# NEOS_CAN.net
KiCad netlist of a schematic drawn in Altium Designer
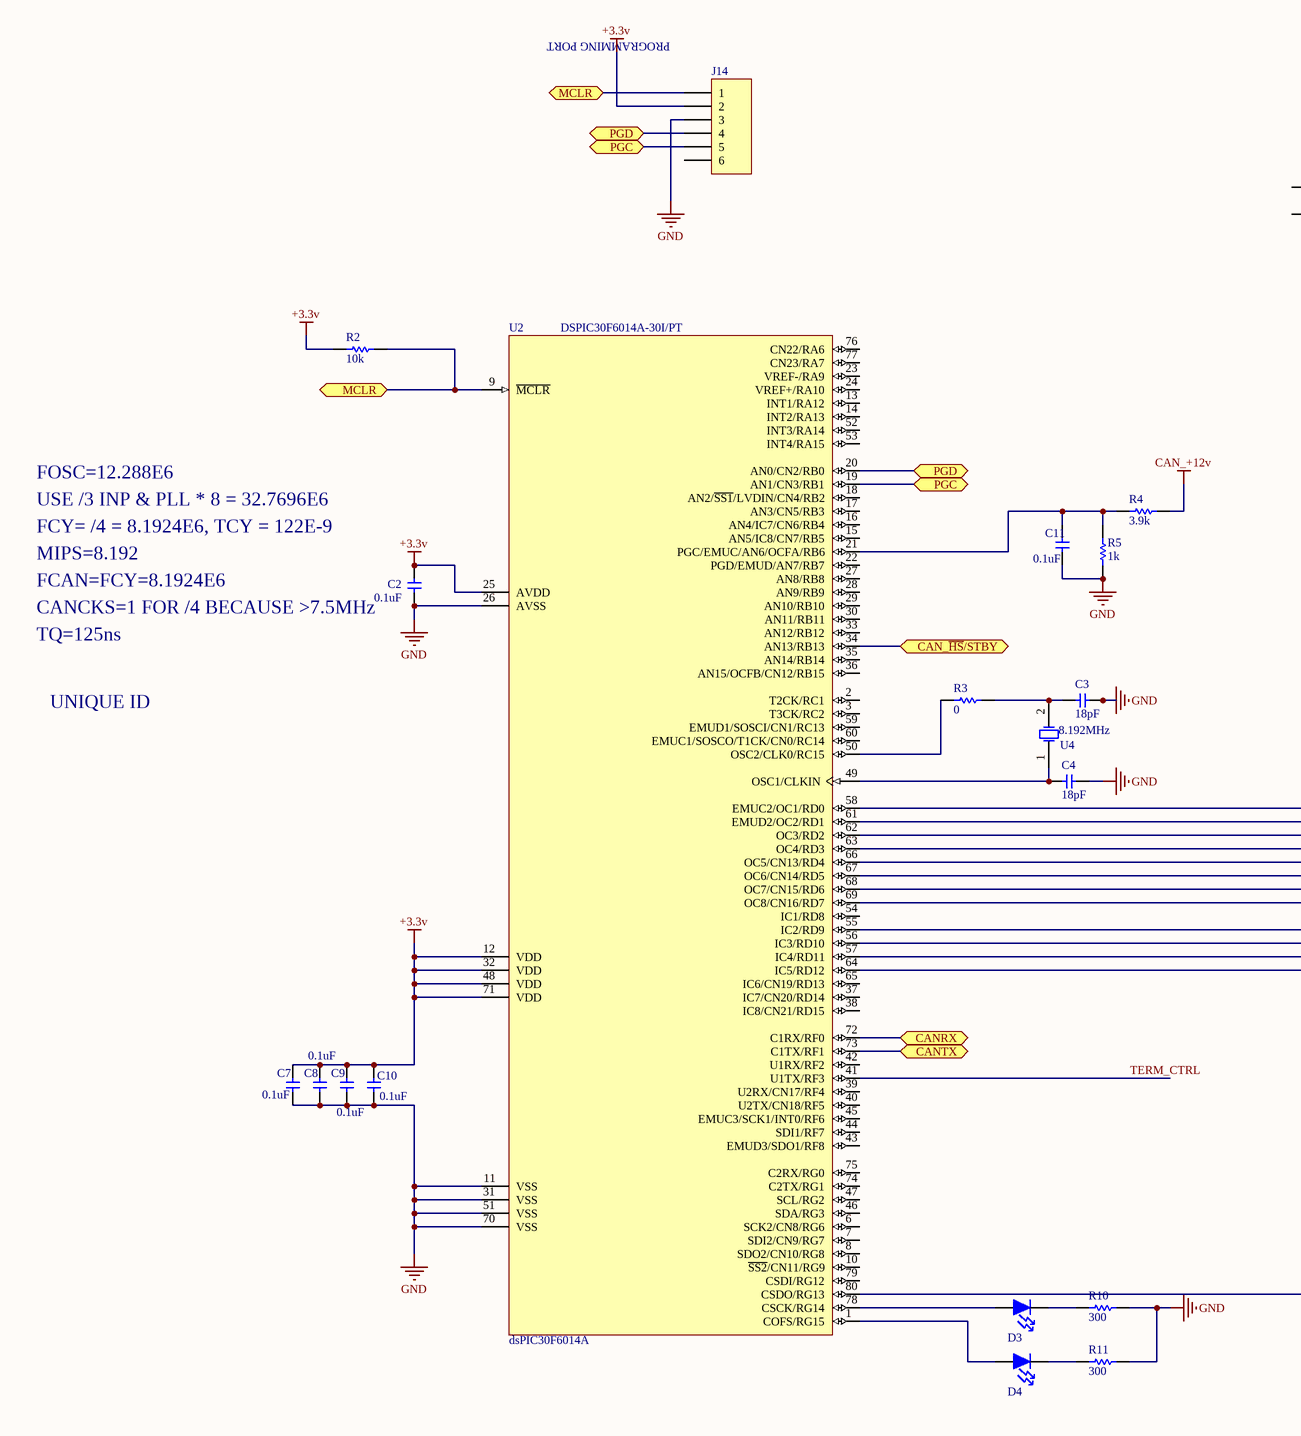
[diagram p0: NEOS_CAN.SchDoc, bottom left]
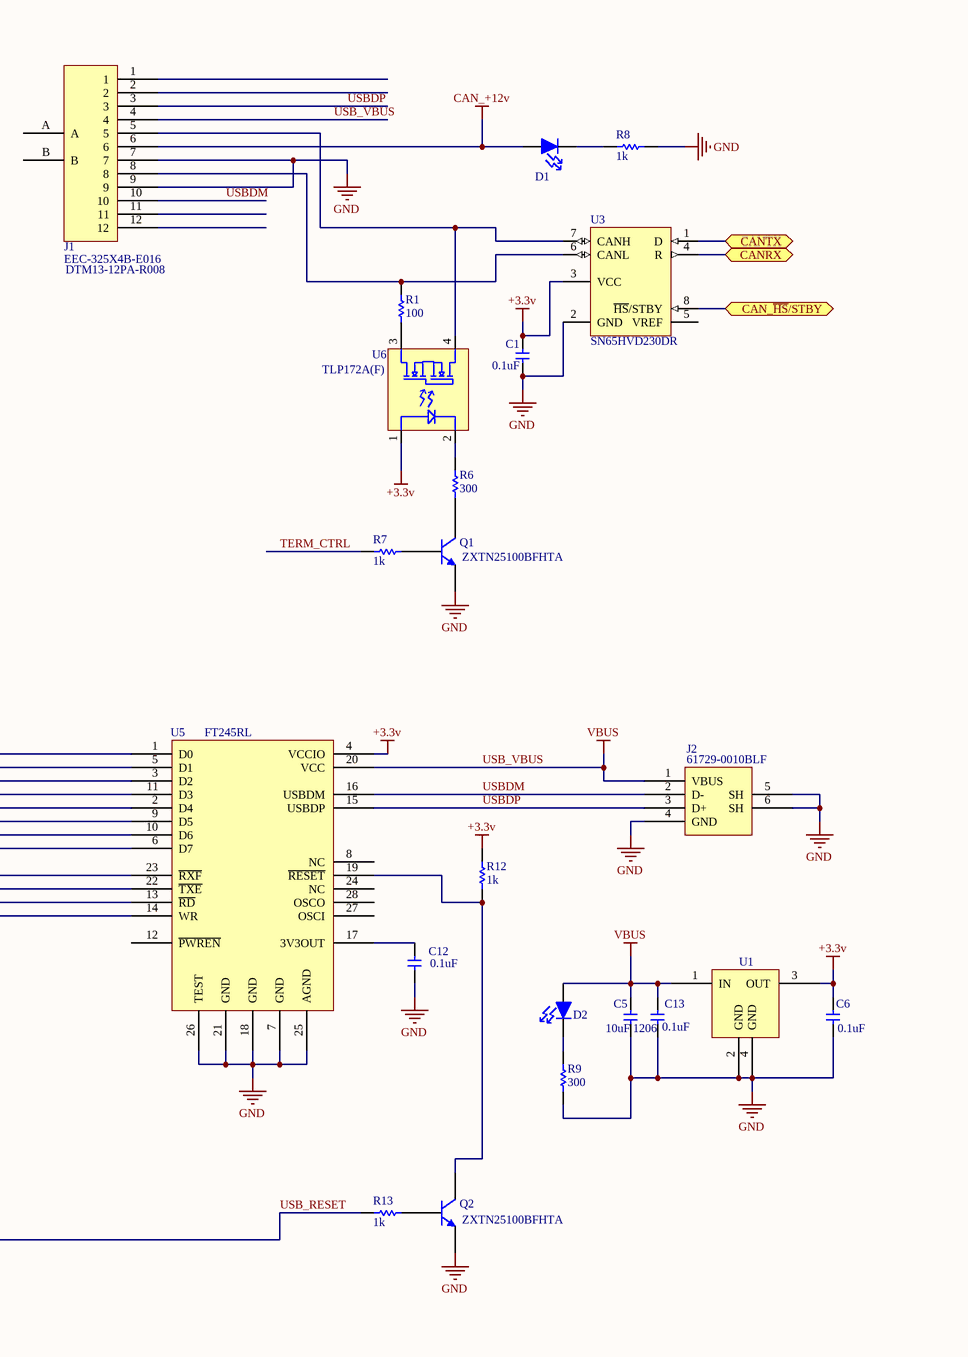
[diagram p1: NEOS_CAN.SchDoc, bottom middle]
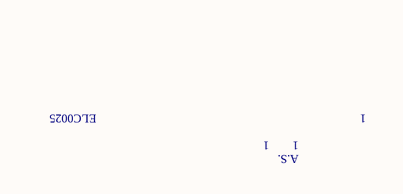
[diagram p2: NEOS_CAN.SchDoc, bottom right]

(export (version "E")
  (design (tool "Eeschema 10.0.6"))
  (components
    (comp (ref "C1")
      (value "0.1uF")
      (footprint "0603")
      (fields
        (field (name "MANUFACTURER") "Murata Electronics North America")
        (field (name "MANUFACTURER PART NUMBER") "GRM188R71C104KA01D")
        (field (name "SOURCE") "Digikey")
      )
      (libsource (lib "PlayworldRCL") (part "C"))
    )
    (comp (ref "C2")
      (value "0.1uF")
      (footprint "0603")
      (fields
        (field (name "MANUFACTURER") "Murata Electronics North America")
        (field (name "MANUFACTURER PART NUMBER") "GRM188R71C104KA01D")
        (field (name "SOURCE") "Digikey")
      )
      (libsource (lib "PlayworldRCL") (part "C"))
    )
    (comp (ref "C3")
      (value "18pF")
      (footprint "0603")
      (description "CAP CER 18PF 50V 5% C0G 0603")
      (fields
        (field (name "MANUFACTURER") "Murata Electronics North America")
        (field (name "MANUFACTURER PART NUMBER") "GRM1885C1H180JA01D")
        (field (name "SOURCE") "Digikey")
      )
      (libsource (lib "PlayworldRCL") (part "C"))
    )
    (comp (ref "C4")
      (value "18pF")
      (footprint "0603")
      (description "CAP CER 18PF 50V 5% C0G 0603")
      (fields
        (field (name "MANUFACTURER") "Murata Electronics North America")
        (field (name "SOURCE") "Digikey")
      )
      (libsource (lib "PlayworldRCL") (part "C"))
    )
    (comp (ref "C5")
      (value "10uF 1206")
      (footprint "1206")
      (fields
        (field (name "MANUFACTURER") "Murata Electronics North America")
        (field (name "MANUFACTURER PART NUMBER") "GRM31CF51E106ZA01L")
        (field (name "Comment") "C")
        (field (name "SOURCE") "Digikey")
      )
      (libsource (lib "PlayworldRCL") (part "C"))
    )
    (comp (ref "C6")
      (value "0.1uF")
      (footprint "0805")
      (fields
        (field (name "MANUFACTURER") "Murata Electronics North America")
        (field (name "MANUFACTURER PART NUMBER") "GRM188R71C104KA01D")
        (field (name "Comment") "C")
        (field (name "SOURCE") "Digikey")
      )
      (libsource (lib "PlayworldRCL") (part "C"))
    )
    (comp (ref "C7")
      (value "0.1uF")
      (footprint "0603")
      (fields
        (field (name "MANUFACTURER") "Murata Electronics North America")
        (field (name "MANUFACTURER PART NUMBER") "GRM188R71C104KA01D")
        (field (name "SOURCE") "Digikey")
      )
      (libsource (lib "PlayworldRCL") (part "C"))
    )
    (comp (ref "C8")
      (value "0.1uF")
      (footprint "0603")
      (fields
        (field (name "MANUFACTURER") "Murata Electronics North America")
        (field (name "MANUFACTURER PART NUMBER") "GRM188R71C104KA01D")
        (field (name "SOURCE") "Digikey")
      )
      (libsource (lib "PlayworldRCL") (part "C"))
    )
    (comp (ref "C9")
      (value "0.1uF")
      (footprint "0603")
      (fields
        (field (name "MANUFACTURER") "Murata Electronics North America")
        (field (name "MANUFACTURER PART NUMBER") "GRM188R71C104KA01D")
        (field (name "SOURCE") "Digikey")
      )
      (libsource (lib "PlayworldRCL") (part "C"))
    )
    (comp (ref "C10")
      (value "0.1uF")
      (footprint "0603")
      (fields
        (field (name "MANUFACTURER") "Murata Electronics North America")
        (field (name "MANUFACTURER PART NUMBER") "GRM188R71C104KA01D")
        (field (name "SOURCE") "Digikey")
      )
      (libsource (lib "PlayworldRCL") (part "C"))
    )
    (comp (ref "C11")
      (value "0.1uF")
      (footprint "0805")
      (fields
        (field (name "MANUFACTURER") "Murata Electronics North America")
        (field (name "MANUFACTURER PART NUMBER") "GRM188R71C104KA01D")
        (field (name "SOURCE") "DIGIKEY")
      )
      (libsource (lib "PlayworldRCL") (part "C"))
    )
    (comp (ref "C12")
      (value "0.1uF")
      (footprint "0805")
      (fields
        (field (name "MANUFACTURER") "Murata Electronics North America")
        (field (name "MANUFACTURER PART NUMBER") "GRM188R71C104KA01D")
        (field (name "Comment") "C")
        (field (name "SOURCE") "Digikey")
      )
      (libsource (lib "PlayworldRCL") (part "C"))
    )
    (comp (ref "C13")
      (value "0.1uF")
      (footprint "0805")
      (fields
        (field (name "MANUFACTURER") "Murata Electronics North America")
        (field (name "MANUFACTURER PART NUMBER") "GRM188R71C104KA01D")
        (field (name "Comment") "C")
        (field (name "SOURCE") "Digikey")
      )
      (libsource (lib "PlayworldRCL") (part "C"))
    )
    (comp (ref "D1")
      (value "LED_0805")
      (footprint "LED_0805")
      (description "LED ALINGAP RED CLEAR 0805 SMD")
      (fields
        (field (name "MANUFACTURER") "Dialight")
        (field (name "MANUFACTURER PART NUMBER") "598-8110-107F")
        (field (name "SOURCE") "Digikey")
      )
      (libsource (lib "PlayworldDiode") (part "LED_0805"))
    )
    (comp (ref "D2")
      (value "LED_0805")
      (footprint "LED_0805")
      (description "LED ALINGAP RED CLEAR 0805 SMD")
      (fields
        (field (name "MANUFACTURER") "Dialight")
        (field (name "MANUFACTURER PART NUMBER") "598-8110-107F")
        (field (name "SOURCE") "Digikey")
      )
      (libsource (lib "PlayworldDiode") (part "LED_0805"))
    )
    (comp (ref "D3")
      (value "LED_0805")
      (footprint "LED_0805")
      (description "LED ALINGAP RED CLEAR 0805 SMD")
      (fields
        (field (name "MANUFACTURER") "Dialight")
        (field (name "MANUFACTURER PART NUMBER") "598-8110-107F")
        (field (name "SOURCE") "Digikey")
      )
      (libsource (lib "PlayworldDiode") (part "LED_0805"))
    )
    (comp (ref "D4")
      (value "LED_0805")
      (footprint "LED_0805")
      (description "LED ALINGAP RED CLEAR 0805 SMD")
      (fields
        (field (name "MANUFACTURER") "Dialight")
        (field (name "MANUFACTURER PART NUMBER") "598-8110-107F")
        (field (name "SOURCE") "Digikey")
      )
      (libsource (lib "PlayworldDiode") (part "LED_0805"))
    )
    (comp (ref "J1")
      (value "DT13-12PA-R008")
      (footprint "DTM13-12PA-R008")
      (description "DTM13-12PA-R008")
      (fields
        (field (name "MANUFACTURER") "Duetsch IPD")
        (field (name "MANUFACTURER PART NUMBER") "DTM13-12PA-R008")
        (field (name "ENCLOSURE PART NUMBER") "EEC-325X4A")
        (field (name "ENCLOSURE PART NUMBER (AMBER)") "EEC-325X4B-E016")
        (field (name "SOURCE") "Ladd Industries")
      )
      (libsource (lib "PlayworldConnector") (part "DT13-12PA-R008"))
    )
    (comp (ref "J2")
      (value "CONN RCPT USB TYPE B R/A PCB")
      (footprint "1-1470156")
      (description "USB TYPE B R/A PCB")
      (fields
        (field (name "MANUFACTURER") "FCI")
        (field (name "MANUFACTURER PART NUMBER") "61729-0010BLF")
        (field (name "SOURCE") "Digikey")
      )
      (libsource (lib "Playworld") (part "USB_TYPEB"))
    )
    (comp (ref "J14")
      (value "CONN HEADER VERT 6POS 5.08MM")
      (footprint "JCPM5086VE0Z")
      (fields
        (field (name "MANUFACTURER") "Phoenix Contact")
        (field (name "MANUFACTURER PART NUMBER") "1758050")
        (field (name "SOURCE") "Digikey")
      )
      (libsource (lib "NEOS_CAN") (part "1758050 - Phoenix 6 Pin Vert. 5.08mm"))
    )
    (comp (ref "Q1")
      (value "ZXTN25100BFHTA")
      (footprint "SOT95P245X145-3L")
      (description "TRANSISTOR NPN 100V 3A SOT-23")
      (fields
        (field (name "MANUFACTURER") "Zetex Inc")
        (field (name "MANUFACTURER PART NUMBER") "ZXTN25100BFHTA")
        (field (name "SOURCE") "Digikey")
      )
      (libsource (lib "PlayworldIC") (part "NPN_SOT23"))
    )
    (comp (ref "Q2")
      (value "ZXTN25100BFHTA")
      (footprint "SOT95P245X145-3L")
      (description "TRANSISTOR NPN 100V 3A SOT-23")
      (fields
        (field (name "MANUFACTURER") "Zetex Inc")
        (field (name "MANUFACTURER PART NUMBER") "ZXTN25100BFHTA")
        (field (name "SOURCE") "Digikey")
      )
      (libsource (lib "PlayworldIC") (part "NPN_SOT23"))
    )
    (comp (ref "R1")
      (value "100")
      (footprint "0805")
      (fields
        (field (name "MANUFACTURER") "Yageo")
        (field (name "MANUFACTURER PART NUMBER") "RC0805FR-07100RL")
        (field (name "SOURCE") "Digikey")
      )
      (libsource (lib "PlayworldRCL") (part "R"))
    )
    (comp (ref "R2")
      (value "10k")
      (footprint "0603")
      (fields
        (field (name "MANUFACTURER") "Yageo")
        (field (name "MANUFACTURER PART NUMBER") "RC0805FR-071KL")
        (field (name "SOURCE") "Digikey")
      )
      (libsource (lib "Playworld") (part "R"))
    )
    (comp (ref "R3")
      (value "0")
      (footprint "0805")
      (fields
        (field (name "MANUFACTURER") "Yageo")
        (field (name "MANUFACTURER PART NUMBER") "RC0603JR-070RL")
        (field (name "SOURCE") "Digikey")
      )
      (libsource (lib "Playworld") (part "R"))
    )
    (comp (ref "R4")
      (value "3.9k")
      (footprint "0805")
      (fields
        (field (name "MANUFACTURER") "Yageo")
        (field (name "MANUFACTURER PART NUMBER") "RC0805FR-073K9L")
        (field (name "SOURCE") "Digikey")
      )
      (libsource (lib "Playworld") (part "R"))
    )
    (comp (ref "R5")
      (value "1k")
      (footprint "0805")
      (fields
        (field (name "MANUFACTURER") "Yageo")
        (field (name "MANUFACTURER PART NUMBER") "RC0805FR-071KL")
        (field (name "SOURCE") "Digikey")
      )
      (libsource (lib "Playworld") (part "R"))
    )
    (comp (ref "R6")
      (value "300")
      (footprint "0805")
      (fields
        (field (name "MANUFACTURER") "Yageo")
        (field (name "MANUFACTURER PART NUMBER") "RC0805FR-07300RL")
        (field (name "Comment") "R")
        (field (name "SOURCE") "Digikey")
      )
      (libsource (lib "Playworld") (part "R"))
    )
    (comp (ref "R7")
      (value "1k")
      (footprint "0805")
      (fields
        (field (name "MANUFACTURER") "Yageo")
        (field (name "MANUFACTURER PART NUMBER") "RC0805FR-071KL")
        (field (name "SOURCE") "Digikey")
      )
      (libsource (lib "Playworld") (part "R"))
    )
    (comp (ref "R8")
      (value "1k")
      (footprint "0805")
      (fields
        (field (name "MANUFACTURER") "Yageo")
        (field (name "MANUFACTURER PART NUMBER") "RC0805FR-071KL")
        (field (name "SOURCE") "Digikey")
      )
      (libsource (lib "Playworld") (part "R"))
    )
    (comp (ref "R9")
      (value "300")
      (footprint "0805")
      (fields
        (field (name "MANUFACTURER") "Yageo")
        (field (name "MANUFACTURER PART NUMBER") "RC0805FR-07300RL")
        (field (name "Comment") "R")
        (field (name "SOURCE") "Digikey")
      )
      (libsource (lib "Playworld") (part "R"))
    )
    (comp (ref "R10")
      (value "300")
      (footprint "0805")
      (fields
        (field (name "MANUFACTURER") "Yageo")
        (field (name "MANUFACTURER PART NUMBER") "RC0805FR-07300RL")
        (field (name "SOURCE") "Digikey")
      )
      (libsource (lib "Playworld") (part "R"))
    )
    (comp (ref "R11")
      (value "300")
      (footprint "0805")
      (fields
        (field (name "MANUFACTURER") "Yageo")
        (field (name "MANUFACTURER PART NUMBER") "RC0805FR-07300RL")
        (field (name "SOURCE") "Digikey")
      )
      (libsource (lib "Playworld") (part "R"))
    )
    (comp (ref "R12")
      (value "1k")
      (footprint "0805")
      (fields
        (field (name "MANUFACTURER") "Panasonic - ECG")
        (field (name "MANUFACTURER PART NUMBER") "RC0805FR-071KL")
        (field (name "SOURCE") "Digikey")
      )
      (libsource (lib "Playworld") (part "R"))
    )
    (comp (ref "R13")
      (value "1k")
      (footprint "0805")
      (fields
        (field (name "MANUFACTURER") "Yageo")
        (field (name "MANUFACTURER PART NUMBER") "RC0805FR-071KL")
        (field (name "SOURCE") "Digikey")
      )
      (libsource (lib "Playworld") (part "R"))
    )
    (comp (ref "U1")
      (value "LM2937")
      (footprint "SOT223")
      (description "IC REG LDO 500MA 3.3V SOT-223")
      (fields
        (field (name "MANUFACTURER") "National Semiconductor")
        (field (name "MANUFACTURER PART NUMBER") "LM2937IMP-3.3/NOPB")
        (field (name "SOURCE") "Digikey")
      )
      (libsource (lib "PlayworldIC") (part "LM2937"))
    )
    (comp (ref "U2")
      (value "dsPIC30F6014A")
      (footprint "PlayworldIC:TQFP-80")
      (description "Microchip dsPIC30F6014 80-TQFP")
      (fields
        (field (name "MANUFACTURER") "Microchip Technology")
        (field (name "MANUFACTURER PART NUMBER") "DSPIC30F6014A-30I/PT")
        (field (name "SOURCE") "Digikey")
      )
      (libsource (lib "PlayworldIC") (part "DSPIC30F6014"))
    )
    (comp (ref "U3")
      (value "SN65HVD230DR")
      (footprint "SOIC 8")
      (description "IC 3.3V CAN TXRX W/STNDBY 8-SOIC")
      (fields (field (name "MANUFACTURER") "Texas Instruments") (field (name "SOURCE") "Digikey"))
      (libsource (lib "PlayworldIC") (part "SN65HVD230DR"))
    )
    (comp (ref "U4")
      (value "8.192MHz")
      (footprint "HCM49")
      (description "CRYSTAL 12.288 MHZ SMT 18PF")
      (fields
        (field (name "MANUFACTURER") "Citizen America Corporation - Component Sales Division")
        (field (name "MANUFACTURER PART NUMBER") "HCM49 12.288MABJ-UT")
        (field (name "SOURCE") "Digikey")
      )
      (libsource (lib "PlayworldIC") (part "CRYSTAL"))
    )
    (comp (ref "U5")
      (value "FT245RL")
      (footprint "SOP65P780X200-28L")
      (description "USB Interface ICs USB TO PARALLEL FIFO 28 PIN SSOP")
      (fields
        (field (name "MANUFACTURER") "FTDI")
        (field (name "MANUFACTURER PART NUMBER") "FT245RL")
        (field (name "SOURCE") "Mouser")
      )
      (libsource (lib "PlayworldIC") (part "FT245RL"))
    )
    (comp (ref "U6")
      (value "TLP172A")
      (footprint "PlayworldIC:PS7241")
      (description "PHOTOCOUPLER PHOTORELAY 4-SOP")
      (fields
        (field (name "MANUFACTURER") "Toshiba")
        (field (name "MANUFACTURER PART NUMBER") "TLP172A(F)")
        (field (name "SOURCE") "Digikey")
      )
      (libsource (lib "PlayworldIC") (part "TLP172A"))
    )
  )
  (nets
    (net (code "1") (name "+3.3v") (class "Default")
      (node (ref "C1") (pin "2") (pinfunction "2_2") (pintype "passive"))
      (node (ref "C10") (pin "2") (pinfunction "2_2") (pintype "passive"))
      (node (ref "C2") (pin "2") (pinfunction "2_2") (pintype "passive"))
      (node (ref "C6") (pin "2") (pinfunction "2_2") (pintype "passive"))
      (node (ref "C7") (pin "2") (pinfunction "2_2") (pintype "passive"))
      (node (ref "C8") (pin "2") (pinfunction "2_2") (pintype "passive"))
      (node (ref "C9") (pin "2") (pinfunction "2_2") (pintype "passive"))
      (node (ref "J14") (pin "2") (pinfunction "2_2") (pintype "passive"))
      (node (ref "R12") (pin "1") (pinfunction "1_1") (pintype "passive"))
      (node (ref "R2") (pin "1") (pinfunction "1_1") (pintype "passive"))
      (node (ref "U1") (pin "3") (pinfunction "OUT_3") (pintype "passive"))
      (node (ref "U2") (pin "12") (pinfunction "VDD_12") (pintype "power_in"))
      (node (ref "U2") (pin "25") (pinfunction "AVDD_25") (pintype "power_in"))
      (node (ref "U2") (pin "32") (pinfunction "VDD_32") (pintype "power_in"))
      (node (ref "U2") (pin "48") (pinfunction "VDD_48") (pintype "power_in"))
      (node (ref "U2") (pin "71") (pinfunction "VDD_71") (pintype "power_in"))
      (node (ref "U3") (pin "3") (pinfunction "VCC_3") (pintype "power_in"))
      (node (ref "U5") (pin "4") (pinfunction "VCCIO_4") (pintype "passive"))
      (node (ref "U6") (pin "1") (pinfunction "1_1") (pintype "passive"))
    )
    (net (code "2") (name "/CANRX") (class "Default")
      (node (ref "U2") (pin "72") (pinfunction "C1RX/RF0_72") (pintype "bidirectional"))
      (node (ref "U3") (pin "4") (pinfunction "R_4") (pintype "output"))
    )
    (net (code "3") (name "/CANTX") (class "Default")
      (node (ref "U2") (pin "73") (pinfunction "C1TX/RF1_73") (pintype "bidirectional"))
      (node (ref "U3") (pin "1") (pinfunction "D_1") (pintype "input"))
    )
    (net (code "4") (name "/CAN_~{HS}{slash}STBY") (class "Default")
      (node (ref "U2") (pin "34") (pinfunction "AN13/RB13_34") (pintype "bidirectional"))
      (node (ref "U3") (pin "8") (pinfunction "~{HS}/STBY_8") (pintype "input"))
    )
    (net (code "5") (name "/MCLR") (class "Default")
      (node (ref "J14") (pin "1") (pinfunction "1_1") (pintype "passive"))
      (node (ref "R2") (pin "2") (pinfunction "2_2") (pintype "passive"))
      (node (ref "U2") (pin "9") (pinfunction "~{MCLR}_9") (pintype "input"))
    )
    (net (code "6") (name "/PGC") (class "Default")
      (node (ref "J14") (pin "5") (pinfunction "5_5") (pintype "passive"))
      (node (ref "U2") (pin "19") (pinfunction "AN1/CN3/RB1_19") (pintype "bidirectional"))
    )
    (net (code "7") (name "/PGD") (class "Default")
      (node (ref "J14") (pin "4") (pinfunction "4_4") (pintype "passive"))
      (node (ref "U2") (pin "20") (pinfunction "AN0/CN2/RB0_20") (pintype "bidirectional"))
    )
    (net (code "8") (name "/TERM_CTRL") (class "Default")
      (node (ref "R7") (pin "2") (pinfunction "2_2") (pintype "passive"))
      (node (ref "U2") (pin "41") (pinfunction "U1TX/RF3_41") (pintype "bidirectional"))
    )
    (net (code "9") (name "/USBDM") (class "Default")
      (node (ref "J1") (pin "10") (pinfunction "10_10") (pintype "passive"))
      (node (ref "J2") (pin "2") (pinfunction "D-_2") (pintype "passive"))
      (node (ref "U5") (pin "16") (pinfunction "USBDM_16") (pintype "passive"))
    )
    (net (code "10") (name "/USBDP") (class "Default")
      (node (ref "J1") (pin "3") (pinfunction "3_3") (pintype "passive"))
      (node (ref "J2") (pin "3") (pinfunction "D+_3") (pintype "passive"))
      (node (ref "U5") (pin "15") (pinfunction "USBDP_15") (pintype "passive"))
    )
    (net (code "11") (name "/USB_RESET") (class "Default")
      (node (ref "R13") (pin "2") (pinfunction "2_2") (pintype "passive"))
      (node (ref "U2") (pin "80") (pinfunction "CSDO/RG13_80") (pintype "bidirectional"))
    )
    (net (code "12") (name "CAN_+12v") (class "Default")
      (node (ref "D1") (pin "A") (pinfunction "A_A") (pintype "passive"))
      (node (ref "J1") (pin "6") (pinfunction "6_6") (pintype "passive"))
      (node (ref "R4") (pin "2") (pinfunction "2_2") (pintype "passive"))
    )
    (net (code "13") (name "GND") (class "Default")
      (node (ref "C1") (pin "1") (pinfunction "1_1") (pintype "passive"))
      (node (ref "C10") (pin "1") (pinfunction "1_1") (pintype "passive"))
      (node (ref "C11") (pin "1") (pinfunction "1_1") (pintype "passive"))
      (node (ref "C12") (pin "2") (pinfunction "2_2") (pintype "passive"))
      (node (ref "C13") (pin "1") (pinfunction "1_1") (pintype "passive"))
      (node (ref "C2") (pin "1") (pinfunction "1_1") (pintype "passive"))
      (node (ref "C3") (pin "1") (pinfunction "1_1") (pintype "passive"))
      (node (ref "C4") (pin "1") (pinfunction "1_1") (pintype "passive"))
      (node (ref "C5") (pin "1") (pinfunction "1_1") (pintype "passive"))
      (node (ref "C6") (pin "1") (pinfunction "1_1") (pintype "passive"))
      (node (ref "C7") (pin "1") (pinfunction "1_1") (pintype "passive"))
      (node (ref "C8") (pin "1") (pinfunction "1_1") (pintype "passive"))
      (node (ref "C9") (pin "1") (pinfunction "1_1") (pintype "passive"))
      (node (ref "J1") (pin "7") (pinfunction "7_7") (pintype "passive"))
      (node (ref "J1") (pin "9") (pinfunction "9_9") (pintype "passive"))
      (node (ref "J14") (pin "3") (pinfunction "3_3") (pintype "passive"))
      (node (ref "J2") (pin "4") (pinfunction "GND_4") (pintype "passive"))
      (node (ref "J2") (pin "5") (pinfunction "SH_5") (pintype "passive"))
      (node (ref "J2") (pin "6") (pinfunction "SH_6") (pintype "passive"))
      (node (ref "Q1") (pin "2") (pinfunction "E_2") (pintype "passive"))
      (node (ref "Q2") (pin "2") (pinfunction "E_2") (pintype "passive"))
      (node (ref "R10") (pin "1") (pinfunction "1_1") (pintype "passive"))
      (node (ref "R11") (pin "1") (pinfunction "1_1") (pintype "passive"))
      (node (ref "R5") (pin "1") (pinfunction "1_1") (pintype "passive"))
      (node (ref "R8") (pin "2") (pinfunction "2_2") (pintype "passive"))
      (node (ref "R9") (pin "1") (pinfunction "1_1") (pintype "passive"))
      (node (ref "U1") (pin "2") (pinfunction "GND_2") (pintype "passive"))
      (node (ref "U1") (pin "4") (pinfunction "GND_4") (pintype "passive"))
      (node (ref "U2") (pin "11") (pinfunction "VSS_11") (pintype "power_in"))
      (node (ref "U2") (pin "26") (pinfunction "AVSS_26") (pintype "power_in"))
      (node (ref "U2") (pin "31") (pinfunction "VSS_31") (pintype "power_in"))
      (node (ref "U2") (pin "51") (pinfunction "VSS_51") (pintype "power_in"))
      (node (ref "U2") (pin "70") (pinfunction "VSS_70") (pintype "power_in"))
      (node (ref "U3") (pin "2") (pinfunction "GND_2") (pintype "power_in"))
      (node (ref "U5") (pin "18") (pinfunction "GND_18") (pintype "passive"))
      (node (ref "U5") (pin "21") (pinfunction "GND_21") (pintype "passive"))
      (node (ref "U5") (pin "25") (pinfunction "AGND_25") (pintype "passive"))
      (node (ref "U5") (pin "26") (pinfunction "TEST_26") (pintype "passive"))
      (node (ref "U5") (pin "7") (pinfunction "GND_7") (pintype "passive"))
    )
    (net (code "14") (name "Net-(D1-PadC)") (class "Default")
      (node (ref "D1") (pin "C") (pinfunction "C_C") (pintype "passive"))
      (node (ref "R8") (pin "1") (pinfunction "1_1") (pintype "passive"))
    )
    (net (code "15") (name "Net-(D2-PadC)") (class "Default")
      (node (ref "D2") (pin "C") (pinfunction "C_C") (pintype "passive"))
      (node (ref "R9") (pin "2") (pinfunction "2_2") (pintype "passive"))
    )
    (net (code "16") (name "Net-(D3-PadC)") (class "Default")
      (node (ref "D3") (pin "C") (pinfunction "C_C") (pintype "passive"))
      (node (ref "R10") (pin "2") (pinfunction "2_2") (pintype "passive"))
    )
    (net (code "17") (name "Net-(D4-PadC)") (class "Default")
      (node (ref "D4") (pin "C") (pinfunction "C_C") (pintype "passive"))
      (node (ref "R11") (pin "2") (pinfunction "2_2") (pintype "passive"))
    )
    (net (code "18") (name "Net-(Q1-B)") (class "Default")
      (node (ref "Q1") (pin "1") (pinfunction "B_1") (pintype "passive"))
      (node (ref "R7") (pin "1") (pinfunction "1_1") (pintype "passive"))
    )
    (net (code "19") (name "Net-(Q1-C)") (class "Default")
      (node (ref "Q1") (pin "3") (pinfunction "C_3") (pintype "passive"))
      (node (ref "R6") (pin "1") (pinfunction "1_1") (pintype "passive"))
    )
    (net (code "20") (name "Net-(Q2-B)") (class "Default")
      (node (ref "Q2") (pin "1") (pinfunction "B_1") (pintype "passive"))
      (node (ref "R13") (pin "1") (pinfunction "1_1") (pintype "passive"))
    )
    (net (code "21") (name "Net-(Q2-C)") (class "Default")
      (node (ref "Q2") (pin "3") (pinfunction "C_3") (pintype "passive"))
      (node (ref "R12") (pin "2") (pinfunction "2_2") (pintype "passive"))
      (node (ref "U5") (pin "19") (pinfunction "~{RESET}_19") (pintype "passive"))
    )
    (net (code "22") (name "Net-(R1-Pad1)") (class "Default")
      (node (ref "R1") (pin "1") (pinfunction "1_1") (pintype "passive"))
      (node (ref "U6") (pin "3") (pinfunction "3_3") (pintype "passive"))
    )
    (net (code "23") (name "Net-(R6-Pad2)") (class "Default")
      (node (ref "R6") (pin "2") (pinfunction "2_2") (pintype "passive"))
      (node (ref "U6") (pin "2") (pinfunction "2_2") (pintype "passive"))
    )
    (net (code "24") (name "Net-(U2-COFS{slash}RG15)") (class "Default")
      (node (ref "D4") (pin "A") (pinfunction "A_A") (pintype "passive"))
      (node (ref "U2") (pin "1") (pinfunction "COFS/RG15_1") (pintype "bidirectional"))
    )
    (net (code "25") (name "Net-(U2-CSCK{slash}RG14)") (class "Default")
      (node (ref "D3") (pin "A") (pinfunction "A_A") (pintype "passive"))
      (node (ref "U2") (pin "78") (pinfunction "CSCK/RG14_78") (pintype "bidirectional"))
    )
    (net (code "26") (name "Net-(U2-EMUC2{slash}OC1{slash}RD0)") (class "Default")
      (node (ref "U2") (pin "58") (pinfunction "EMUC2/OC1/RD0_58") (pintype "bidirectional"))
      (node (ref "U5") (pin "1") (pinfunction "D0_1") (pintype "passive"))
    )
    (net (code "27") (name "Net-(U2-EMUD2{slash}OC2{slash}RD1)") (class "Default")
      (node (ref "U2") (pin "61") (pinfunction "EMUD2/OC2/RD1_61") (pintype "bidirectional"))
      (node (ref "U5") (pin "5") (pinfunction "D1_5") (pintype "passive"))
    )
    (net (code "28") (name "Net-(U2-IC2{slash}RD9)") (class "Default")
      (node (ref "U2") (pin "55") (pinfunction "IC2/RD9_55") (pintype "bidirectional"))
      (node (ref "U5") (pin "23") (pinfunction "~{RXF}_23") (pintype "passive"))
    )
    (net (code "29") (name "Net-(U2-IC3{slash}RD10)") (class "Default")
      (node (ref "U2") (pin "56") (pinfunction "IC3/RD10_56") (pintype "bidirectional"))
      (node (ref "U5") (pin "22") (pinfunction "~{TXE}_22") (pintype "passive"))
    )
    (net (code "30") (name "Net-(U2-IC4{slash}RD11)") (class "Default")
      (node (ref "U2") (pin "57") (pinfunction "IC4/RD11_57") (pintype "bidirectional"))
      (node (ref "U5") (pin "13") (pinfunction "~{RD}_13") (pintype "passive"))
    )
    (net (code "31") (name "Net-(U2-IC5{slash}RD12)") (class "Default")
      (node (ref "U2") (pin "64") (pinfunction "IC5/RD12_64") (pintype "bidirectional"))
      (node (ref "U5") (pin "14") (pinfunction "WR_14") (pintype "passive"))
    )
    (net (code "32") (name "Net-(U2-OC3{slash}RD2)") (class "Default")
      (node (ref "U2") (pin "62") (pinfunction "OC3/RD2_62") (pintype "bidirectional"))
      (node (ref "U5") (pin "3") (pinfunction "D2_3") (pintype "passive"))
    )
    (net (code "33") (name "Net-(U2-OC4{slash}RD3)") (class "Default")
      (node (ref "U2") (pin "63") (pinfunction "OC4/RD3_63") (pintype "bidirectional"))
      (node (ref "U5") (pin "11") (pinfunction "D3_11") (pintype "passive"))
    )
    (net (code "34") (name "Net-(U2-OC5{slash}CN13{slash}RD4)") (class "Default")
      (node (ref "U2") (pin "66") (pinfunction "OC5/CN13/RD4_66") (pintype "bidirectional"))
      (node (ref "U5") (pin "2") (pinfunction "D4_2") (pintype "passive"))
    )
    (net (code "35") (name "Net-(U2-OC6{slash}CN14{slash}RD5)") (class "Default")
      (node (ref "U2") (pin "67") (pinfunction "OC6/CN14/RD5_67") (pintype "bidirectional"))
      (node (ref "U5") (pin "9") (pinfunction "D5_9") (pintype "passive"))
    )
    (net (code "36") (name "Net-(U2-OC7{slash}CN15{slash}RD6)") (class "Default")
      (node (ref "U2") (pin "68") (pinfunction "OC7/CN15/RD6_68") (pintype "bidirectional"))
      (node (ref "U5") (pin "10") (pinfunction "D6_10") (pintype "passive"))
    )
    (net (code "37") (name "Net-(U2-OC8{slash}CN16{slash}RD7)") (class "Default")
      (node (ref "U2") (pin "69") (pinfunction "OC8/CN16/RD7_69") (pintype "bidirectional"))
      (node (ref "U5") (pin "6") (pinfunction "D7_6") (pintype "passive"))
    )
    (net (code "38") (name "Net-(U2-OSC1{slash}CLKIN)") (class "Default")
      (node (ref "C4") (pin "2") (pinfunction "2_2") (pintype "passive"))
      (node (ref "U2") (pin "49") (pinfunction "OSC1/CLKIN_49") (pintype "input"))
      (node (ref "U4") (pin "1") (pinfunction "OSC1_1") (pintype "passive"))
    )
    (net (code "39") (name "Net-(U2-OSC2{slash}CLK0{slash}RC15)") (class "Default")
      (node (ref "R3") (pin "1") (pinfunction "1_1") (pintype "passive"))
      (node (ref "U2") (pin "50") (pinfunction "OSC2/CLK0/RC15_50") (pintype "bidirectional"))
    )
    (net (code "40") (name "Net-(U2-PGC{slash}EMUC{slash}AN6{slash}OCFA{slash}RB6)") (class "Default")
      (node (ref "C11") (pin "2") (pinfunction "2_2") (pintype "passive"))
      (node (ref "R4") (pin "1") (pinfunction "1_1") (pintype "passive"))
      (node (ref "R5") (pin "2") (pinfunction "2_2") (pintype "passive"))
      (node (ref "U2") (pin "21") (pinfunction "PGC/EMUC/AN6/OCFA/RB6_21") (pintype "bidirectional"))
    )
    (net (code "41") (name "Net-(U3-CANH)") (class "Default")
      (node (ref "J1") (pin "5") (pinfunction "5_5") (pintype "passive"))
      (node (ref "U3") (pin "7") (pinfunction "CANH_7") (pintype "bidirectional"))
      (node (ref "U6") (pin "4") (pinfunction "4_4") (pintype "passive"))
    )
    (net (code "42") (name "Net-(U3-CANL)") (class "Default")
      (node (ref "J1") (pin "8") (pinfunction "8_8") (pintype "passive"))
      (node (ref "R1") (pin "2") (pinfunction "2_2") (pintype "passive"))
      (node (ref "U3") (pin "6") (pinfunction "CANL_6") (pintype "bidirectional"))
    )
    (net (code "43") (name "Net-(U4-OSC2)") (class "Default")
      (node (ref "C3") (pin "2") (pinfunction "2_2") (pintype "passive"))
      (node (ref "R3") (pin "2") (pinfunction "2_2") (pintype "passive"))
      (node (ref "U4") (pin "2") (pinfunction "OSC2_2") (pintype "passive"))
    )
    (net (code "44") (name "Net-(U5-3V3OUT)") (class "Default")
      (node (ref "C12") (pin "1") (pinfunction "1_1") (pintype "passive"))
      (node (ref "U5") (pin "17") (pinfunction "3V3OUT_17") (pintype "passive"))
    )
    (net (code "45") (name "VBUS") (class "Default")
      (node (ref "C13") (pin "2") (pinfunction "2_2") (pintype "passive"))
      (node (ref "C5") (pin "2") (pinfunction "2_2") (pintype "passive"))
      (node (ref "D2") (pin "A") (pinfunction "A_A") (pintype "passive"))
      (node (ref "J1") (pin "4") (pinfunction "4_4") (pintype "passive"))
      (node (ref "J2") (pin "1") (pinfunction "VBUS_1") (pintype "passive"))
      (node (ref "U1") (pin "1") (pinfunction "IN_1") (pintype "passive"))
      (node (ref "U5") (pin "20") (pinfunction "VCC_20") (pintype "passive"))
    )
    (net (code "46") (name "unconnected-(J1-Pad1)") (class "Default")
      (node (ref "J1") (pin "1") (pinfunction "1_1") (pintype "passive"))
    )
    (net (code "47") (name "unconnected-(J1-Pad2)") (class "Default")
      (node (ref "J1") (pin "2") (pinfunction "2_2") (pintype "passive"))
    )
    (net (code "48") (name "unconnected-(J1-Pad11)") (class "Default")
      (node (ref "J1") (pin "11") (pinfunction "11_11") (pintype "passive"))
    )
    (net (code "49") (name "unconnected-(J1-Pad12)") (class "Default")
      (node (ref "J1") (pin "12") (pinfunction "12_12") (pintype "passive"))
    )
    (net (code "50") (name "unconnected-(J1-PadA)") (class "Default")
      (node (ref "J1") (pin "A") (pinfunction "A_A") (pintype "passive"))
    )
    (net (code "51") (name "unconnected-(J1-PadB)") (class "Default")
      (node (ref "J1") (pin "B") (pinfunction "B_B") (pintype "passive"))
    )
    (net (code "52") (name "unconnected-(J14-Pad6)") (class "Default")
      (node (ref "J14") (pin "6") (pinfunction "6_6") (pintype "passive"))
    )
    (net (code "53") (name "unconnected-(U2-AN2{slash}~{SS1}{slash}LVDIN{slash}CN4{slash}RB2-Pad18)") (class "Default")
      (node (ref "U2") (pin "18") (pinfunction "AN2/~{SS1}/LVDIN/CN4/RB2_18") (pintype "bidirectional"))
    )
    (net (code "54") (name "unconnected-(U2-AN3{slash}CN5{slash}RB3-Pad17)") (class "Default")
      (node (ref "U2") (pin "17") (pinfunction "AN3/CN5/RB3_17") (pintype "bidirectional"))
    )
    (net (code "55") (name "unconnected-(U2-AN4{slash}IC7{slash}CN6{slash}RB4-Pad16)") (class "Default")
      (node (ref "U2") (pin "16") (pinfunction "AN4/IC7/CN6/RB4_16") (pintype "bidirectional"))
    )
    (net (code "56") (name "unconnected-(U2-AN5{slash}IC8{slash}CN7{slash}RB5-Pad15)") (class "Default")
      (node (ref "U2") (pin "15") (pinfunction "AN5/IC8/CN7/RB5_15") (pintype "bidirectional"))
    )
    (net (code "57") (name "unconnected-(U2-AN8{slash}RB8-Pad27)") (class "Default")
      (node (ref "U2") (pin "27") (pinfunction "AN8/RB8_27") (pintype "bidirectional"))
    )
    (net (code "58") (name "unconnected-(U2-AN9{slash}RB9-Pad28)") (class "Default")
      (node (ref "U2") (pin "28") (pinfunction "AN9/RB9_28") (pintype "bidirectional"))
    )
    (net (code "59") (name "unconnected-(U2-AN10{slash}RB10-Pad29)") (class "Default")
      (node (ref "U2") (pin "29") (pinfunction "AN10/RB10_29") (pintype "bidirectional"))
    )
    (net (code "60") (name "unconnected-(U2-AN11{slash}RB11-Pad30)") (class "Default")
      (node (ref "U2") (pin "30") (pinfunction "AN11/RB11_30") (pintype "bidirectional"))
    )
    (net (code "61") (name "unconnected-(U2-AN12{slash}RB12-Pad33)") (class "Default")
      (node (ref "U2") (pin "33") (pinfunction "AN12/RB12_33") (pintype "bidirectional"))
    )
    (net (code "62") (name "unconnected-(U2-AN14{slash}RB14-Pad35)") (class "Default")
      (node (ref "U2") (pin "35") (pinfunction "AN14/RB14_35") (pintype "bidirectional"))
    )
    (net (code "63") (name "unconnected-(U2-AN15{slash}OCFB{slash}CN12{slash}RB15-Pad36)") (class "Default")
      (node (ref "U2") (pin "36") (pinfunction "AN15/OCFB/CN12/RB15_36") (pintype "bidirectional"))
    )
    (net (code "64") (name "unconnected-(U2-C2RX{slash}RG0-Pad75)") (class "Default")
      (node (ref "U2") (pin "75") (pinfunction "C2RX/RG0_75") (pintype "bidirectional"))
    )
    (net (code "65") (name "unconnected-(U2-C2TX{slash}RG1-Pad74)") (class "Default")
      (node (ref "U2") (pin "74") (pinfunction "C2TX/RG1_74") (pintype "bidirectional"))
    )
    (net (code "66") (name "unconnected-(U2-CN22{slash}RA6-Pad76)") (class "Default")
      (node (ref "U2") (pin "76") (pinfunction "CN22/RA6_76") (pintype "bidirectional"))
    )
    (net (code "67") (name "unconnected-(U2-CN23{slash}RA7-Pad77)") (class "Default")
      (node (ref "U2") (pin "77") (pinfunction "CN23/RA7_77") (pintype "bidirectional"))
    )
    (net (code "68") (name "unconnected-(U2-CSDI{slash}RG12-Pad79)") (class "Default")
      (node (ref "U2") (pin "79") (pinfunction "CSDI/RG12_79") (pintype "bidirectional"))
    )
    (net (code "69") (name "unconnected-(U2-EMUC1{slash}SOSCO{slash}T1CK{slash}CN0{slash}RC14-Pad60)") (class "Default")
      (node (ref "U2") (pin "60") (pinfunction "EMUC1/SOSCO/T1CK/CN0/RC14_60") (pintype "bidirectional"))
    )
    (net (code "70") (name "unconnected-(U2-EMUC3{slash}SCK1{slash}INT0{slash}RF6-Pad45)") (class "Default")
      (node (ref "U2") (pin "45") (pinfunction "EMUC3/SCK1/INT0/RF6_45") (pintype "bidirectional"))
    )
    (net (code "71") (name "unconnected-(U2-EMUD1{slash}SOSCI{slash}CN1{slash}RC13-Pad59)") (class "Default")
      (node (ref "U2") (pin "59") (pinfunction "EMUD1/SOSCI/CN1/RC13_59") (pintype "bidirectional"))
    )
    (net (code "72") (name "unconnected-(U2-EMUD3{slash}SDO1{slash}RF8-Pad43)") (class "Default")
      (node (ref "U2") (pin "43") (pinfunction "EMUD3/SDO1/RF8_43") (pintype "bidirectional"))
    )
    (net (code "73") (name "unconnected-(U2-IC1{slash}RD8-Pad54)") (class "Default")
      (node (ref "U2") (pin "54") (pinfunction "IC1/RD8_54") (pintype "bidirectional"))
    )
    (net (code "74") (name "unconnected-(U2-IC6{slash}CN19{slash}RD13-Pad65)") (class "Default")
      (node (ref "U2") (pin "65") (pinfunction "IC6/CN19/RD13_65") (pintype "bidirectional"))
    )
    (net (code "75") (name "unconnected-(U2-IC7{slash}CN20{slash}RD14-Pad37)") (class "Default")
      (node (ref "U2") (pin "37") (pinfunction "IC7/CN20/RD14_37") (pintype "bidirectional"))
    )
    (net (code "76") (name "unconnected-(U2-IC8{slash}CN21{slash}RD15-Pad38)") (class "Default")
      (node (ref "U2") (pin "38") (pinfunction "IC8/CN21/RD15_38") (pintype "bidirectional"))
    )
    (net (code "77") (name "unconnected-(U2-INT1{slash}RA12-Pad13)") (class "Default")
      (node (ref "U2") (pin "13") (pinfunction "INT1/RA12_13") (pintype "bidirectional"))
    )
    (net (code "78") (name "unconnected-(U2-INT2{slash}RA13-Pad14)") (class "Default")
      (node (ref "U2") (pin "14") (pinfunction "INT2/RA13_14") (pintype "bidirectional"))
    )
    (net (code "79") (name "unconnected-(U2-INT3{slash}RA14-Pad52)") (class "Default")
      (node (ref "U2") (pin "52") (pinfunction "INT3/RA14_52") (pintype "bidirectional"))
    )
    (net (code "80") (name "unconnected-(U2-INT4{slash}RA15-Pad53)") (class "Default")
      (node (ref "U2") (pin "53") (pinfunction "INT4/RA15_53") (pintype "bidirectional"))
    )
    (net (code "81") (name "unconnected-(U2-PGD{slash}EMUD{slash}AN7{slash}RB7-Pad22)") (class "Default")
      (node (ref "U2") (pin "22") (pinfunction "PGD/EMUD/AN7/RB7_22") (pintype "bidirectional"))
    )
    (net (code "82") (name "unconnected-(U2-SCK2{slash}CN8{slash}RG6-Pad6)") (class "Default")
      (node (ref "U2") (pin "6") (pinfunction "SCK2/CN8/RG6_6") (pintype "bidirectional"))
    )
    (net (code "83") (name "unconnected-(U2-SCL{slash}RG2-Pad47)") (class "Default")
      (node (ref "U2") (pin "47") (pinfunction "SCL/RG2_47") (pintype "bidirectional"))
    )
    (net (code "84") (name "unconnected-(U2-SDA{slash}RG3-Pad46)") (class "Default")
      (node (ref "U2") (pin "46") (pinfunction "SDA/RG3_46") (pintype "bidirectional"))
    )
    (net (code "85") (name "unconnected-(U2-SDI1{slash}RF7-Pad44)") (class "Default")
      (node (ref "U2") (pin "44") (pinfunction "SDI1/RF7_44") (pintype "bidirectional"))
    )
    (net (code "86") (name "unconnected-(U2-SDI2{slash}CN9{slash}RG7-Pad7)") (class "Default")
      (node (ref "U2") (pin "7") (pinfunction "SDI2/CN9/RG7_7") (pintype "bidirectional"))
    )
    (net (code "87") (name "unconnected-(U2-SDO2{slash}CN10{slash}RG8-Pad8)") (class "Default")
      (node (ref "U2") (pin "8") (pinfunction "SDO2/CN10/RG8_8") (pintype "bidirectional"))
    )
    (net (code "88") (name "unconnected-(U2-T2CK{slash}RC1-Pad2)") (class "Default")
      (node (ref "U2") (pin "2") (pinfunction "T2CK/RC1_2") (pintype "bidirectional"))
    )
    (net (code "89") (name "unconnected-(U2-T3CK{slash}RC2-Pad3)") (class "Default")
      (node (ref "U2") (pin "3") (pinfunction "T3CK/RC2_3") (pintype "bidirectional"))
    )
    (net (code "90") (name "unconnected-(U2-U1RX{slash}RF2-Pad42)") (class "Default")
      (node (ref "U2") (pin "42") (pinfunction "U1RX/RF2_42") (pintype "bidirectional"))
    )
    (net (code "91") (name "unconnected-(U2-U2RX{slash}CN17{slash}RF4-Pad39)") (class "Default")
      (node (ref "U2") (pin "39") (pinfunction "U2RX/CN17/RF4_39") (pintype "bidirectional"))
    )
    (net (code "92") (name "unconnected-(U2-U2TX{slash}CN18{slash}RF5-Pad40)") (class "Default")
      (node (ref "U2") (pin "40") (pinfunction "U2TX/CN18/RF5_40") (pintype "bidirectional"))
    )
    (net (code "93") (name "unconnected-(U2-VREF+{slash}RA10-Pad24)") (class "Default")
      (node (ref "U2") (pin "24") (pinfunction "VREF+/RA10_24") (pintype "bidirectional"))
    )
    (net (code "94") (name "unconnected-(U2-VREF-{slash}RA9-Pad23)") (class "Default")
      (node (ref "U2") (pin "23") (pinfunction "VREF-/RA9_23") (pintype "bidirectional"))
    )
    (net (code "95") (name "unconnected-(U2-~{SS2}{slash}CN11{slash}RG9-Pad10)") (class "Default")
      (node (ref "U2") (pin "10") (pinfunction "~{SS2}/CN11/RG9_10") (pintype "bidirectional"))
    )
    (net (code "96") (name "unconnected-(U3-VREF-Pad5)") (class "Default")
      (node (ref "U3") (pin "5") (pinfunction "VREF_5") (pintype "passive"))
    )
    (net (code "97") (name "unconnected-(U5-NC-Pad8)") (class "Default")
      (node (ref "U5") (pin "8") (pinfunction "NC_8") (pintype "passive"))
    )
    (net (code "98") (name "unconnected-(U5-NC-Pad24)") (class "Default")
      (node (ref "U5") (pin "24") (pinfunction "NC_24") (pintype "passive"))
    )
    (net (code "99") (name "unconnected-(U5-OSCI-Pad27)") (class "Default")
      (node (ref "U5") (pin "27") (pinfunction "OSCI_27") (pintype "passive"))
    )
    (net (code "100") (name "unconnected-(U5-OSCO-Pad28)") (class "Default")
      (node (ref "U5") (pin "28") (pinfunction "OSCO_28") (pintype "passive"))
    )
    (net (code "101") (name "unconnected-(U5-~{PWREN}-Pad12)") (class "Default")
      (node (ref "U5") (pin "12") (pinfunction "~{PWREN}_12") (pintype "passive"))
    )
  )
)
